# nttb.net
KiCad netlist of a schematic drawn in EAGLE
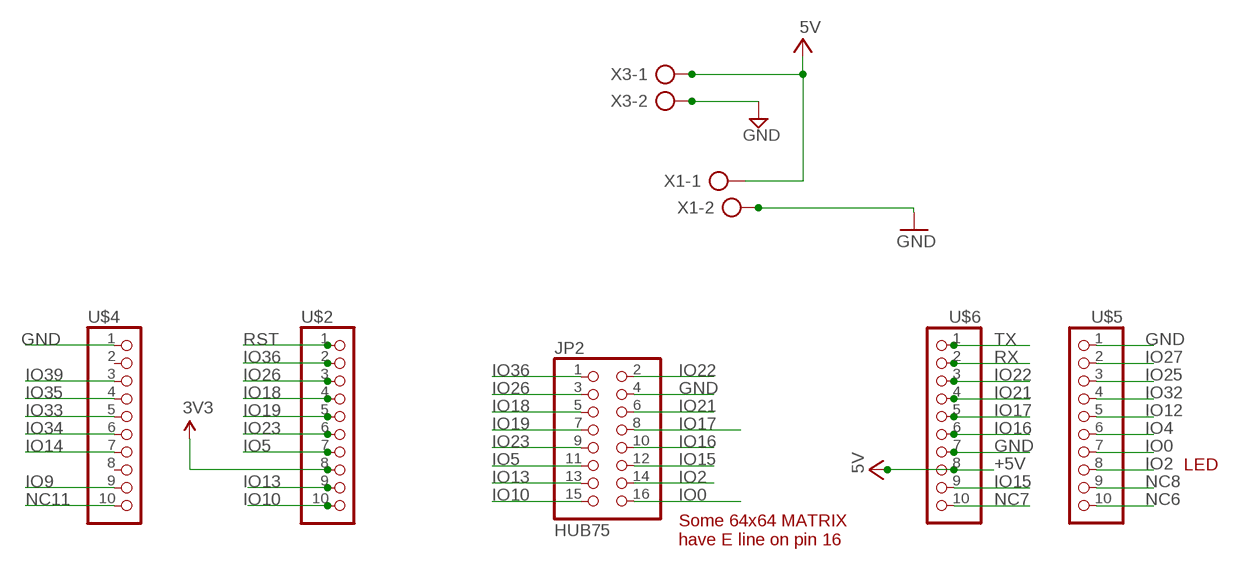
[diagram p0: schematic, sheet 1]

(export (version "E")
  (design (tool "Eeschema 10.0.6"))
  (components
    (comp (ref "JP2")
      (value "HUB75")
      (footprint "eagle-import:2X08")
      (libsource (lib "eagle-import") (part "HEADER-2X8"))
    )
    (comp (ref "U$2")
      (value "PINHD-1X10")
      (footprint "eagle-import:1X10-BIG")
      (libsource (lib "eagle-import") (part "PINHD-1X10"))
    )
    (comp (ref "U$4")
      (value "PINHD-1X10")
      (footprint "eagle-import:1X10-BIG")
      (libsource (lib "eagle-import") (part "PINHD-1X10"))
    )
    (comp (ref "U$5")
      (value "PINHD-1X10")
      (footprint "eagle-import:1X10-BIG")
      (libsource (lib "eagle-import") (part "PINHD-1X10"))
    )
    (comp (ref "U$6")
      (value "PINHD-1X10")
      (footprint "eagle-import:1X10-BIG")
      (libsource (lib "eagle-import") (part "PINHD-1X10"))
    )
    (comp (ref "X1")
      (value "AK500/2")
      (footprint "eagle-import:AK500_2")
      (libsource (lib "eagle-import") (part "AK500/2"))
    )
    (comp (ref "X3")
      (value "AK500/2")
      (footprint "eagle-import:AK500_2")
      (libsource (lib "eagle-import") (part "AK500/2"))
    )
  )
  (nets
    (net (code "1") (name "/IO0") (class "Default")
      (node (ref "JP2") (pin "16") (pinfunction "16_16") (pintype "passive"))
      (node (ref "U$5") (pin "7") (pinfunction "7_7") (pintype "passive"))
    )
    (net (code "2") (name "/IO2") (class "Default")
      (node (ref "JP2") (pin "14") (pinfunction "14_14") (pintype "passive"))
      (node (ref "U$5") (pin "8") (pinfunction "8_8") (pintype "passive"))
    )
    (net (code "3") (name "/IO4") (class "Default")
      (node (ref "U$5") (pin "6") (pinfunction "6_6") (pintype "passive"))
    )
    (net (code "4") (name "/IO5") (class "Default")
      (node (ref "JP2") (pin "11") (pinfunction "11_11") (pintype "passive"))
      (node (ref "U$2") (pin "7") (pinfunction "7_7") (pintype "passive"))
    )
    (net (code "5") (name "/IO9") (class "Default")
      (node (ref "U$4") (pin "9") (pinfunction "9_9") (pintype "passive"))
    )
    (net (code "6") (name "/IO10") (class "Default")
      (node (ref "JP2") (pin "15") (pinfunction "15_15") (pintype "passive"))
      (node (ref "U$2") (pin "10") (pinfunction "10_10") (pintype "passive"))
    )
    (net (code "7") (name "/IO12") (class "Default")
      (node (ref "U$5") (pin "5") (pinfunction "5_5") (pintype "passive"))
    )
    (net (code "8") (name "/IO13") (class "Default")
      (node (ref "JP2") (pin "13") (pinfunction "13_13") (pintype "passive"))
      (node (ref "U$2") (pin "9") (pinfunction "9_9") (pintype "passive"))
    )
    (net (code "9") (name "/IO14") (class "Default")
      (node (ref "U$4") (pin "7") (pinfunction "7_7") (pintype "passive"))
    )
    (net (code "10") (name "/IO15") (class "Default")
      (node (ref "JP2") (pin "12") (pinfunction "12_12") (pintype "passive"))
      (node (ref "U$6") (pin "9") (pinfunction "9_9") (pintype "passive"))
    )
    (net (code "11") (name "/IO16") (class "Default")
      (node (ref "JP2") (pin "10") (pinfunction "10_10") (pintype "passive"))
      (node (ref "U$6") (pin "6") (pinfunction "6_6") (pintype "passive"))
    )
    (net (code "12") (name "/IO17") (class "Default")
      (node (ref "JP2") (pin "8") (pinfunction "8_8") (pintype "passive"))
      (node (ref "U$6") (pin "5") (pinfunction "5_5") (pintype "passive"))
    )
    (net (code "13") (name "/IO18") (class "Default")
      (node (ref "JP2") (pin "5") (pinfunction "5_5") (pintype "passive"))
      (node (ref "U$2") (pin "4") (pinfunction "4_4") (pintype "passive"))
    )
    (net (code "14") (name "/IO19") (class "Default")
      (node (ref "JP2") (pin "7") (pinfunction "7_7") (pintype "passive"))
      (node (ref "U$2") (pin "5") (pinfunction "5_5") (pintype "passive"))
    )
    (net (code "15") (name "/IO21") (class "Default")
      (node (ref "JP2") (pin "6") (pinfunction "6_6") (pintype "passive"))
      (node (ref "U$6") (pin "4") (pinfunction "4_4") (pintype "passive"))
    )
    (net (code "16") (name "/IO22") (class "Default")
      (node (ref "JP2") (pin "2") (pinfunction "2_2") (pintype "passive"))
      (node (ref "U$6") (pin "3") (pinfunction "3_3") (pintype "passive"))
    )
    (net (code "17") (name "/IO23") (class "Default")
      (node (ref "JP2") (pin "9") (pinfunction "9_9") (pintype "passive"))
      (node (ref "U$2") (pin "6") (pinfunction "6_6") (pintype "passive"))
    )
    (net (code "18") (name "/IO25") (class "Default")
      (node (ref "U$5") (pin "3") (pinfunction "3_3") (pintype "passive"))
    )
    (net (code "19") (name "/IO26") (class "Default")
      (node (ref "JP2") (pin "3") (pinfunction "3_3") (pintype "passive"))
      (node (ref "U$2") (pin "3") (pinfunction "3_3") (pintype "passive"))
    )
    (net (code "20") (name "/IO27") (class "Default")
      (node (ref "U$5") (pin "2") (pinfunction "2_2") (pintype "passive"))
    )
    (net (code "21") (name "/IO32") (class "Default")
      (node (ref "U$5") (pin "4") (pinfunction "4_4") (pintype "passive"))
    )
    (net (code "22") (name "/IO33") (class "Default")
      (node (ref "U$4") (pin "5") (pinfunction "5_5") (pintype "passive"))
    )
    (net (code "23") (name "/IO34") (class "Default")
      (node (ref "U$4") (pin "6") (pinfunction "6_6") (pintype "passive"))
    )
    (net (code "24") (name "/IO35") (class "Default")
      (node (ref "U$4") (pin "4") (pinfunction "4_4") (pintype "passive"))
    )
    (net (code "25") (name "/IO36") (class "Default")
      (node (ref "JP2") (pin "1") (pinfunction "1_1") (pintype "passive"))
      (node (ref "U$2") (pin "2") (pinfunction "2_2") (pintype "passive"))
    )
    (net (code "26") (name "/IO39") (class "Default")
      (node (ref "U$4") (pin "3") (pinfunction "3_3") (pintype "passive"))
    )
    (net (code "27") (name "/NC6") (class "Default")
      (node (ref "U$5") (pin "10") (pinfunction "10_10") (pintype "passive"))
    )
    (net (code "28") (name "/NC7") (class "Default")
      (node (ref "U$6") (pin "10") (pinfunction "10_10") (pintype "passive"))
    )
    (net (code "29") (name "/NC8") (class "Default")
      (node (ref "U$5") (pin "9") (pinfunction "9_9") (pintype "passive"))
    )
    (net (code "30") (name "/NC11") (class "Default")
      (node (ref "U$4") (pin "10") (pinfunction "10_10") (pintype "passive"))
    )
    (net (code "31") (name "/RST") (class "Default")
      (node (ref "U$2") (pin "1") (pinfunction "1_1") (pintype "passive"))
    )
    (net (code "32") (name "/RX") (class "Default")
      (node (ref "U$6") (pin "2") (pinfunction "2_2") (pintype "passive"))
    )
    (net (code "33") (name "/TX") (class "Default")
      (node (ref "U$6") (pin "1") (pinfunction "1_1") (pintype "passive"))
    )
    (net (code "34") (name "3V3") (class "Default")
      (node (ref "U$2") (pin "8") (pinfunction "8_8") (pintype "passive"))
    )
    (net (code "35") (name "5V") (class "Default")
      (node (ref "U$6") (pin "8") (pinfunction "8_8") (pintype "passive"))
      (node (ref "X1") (pin "1") (pinfunction "KL_1") (pintype "passive"))
      (node (ref "X3") (pin "1") (pinfunction "KL_1") (pintype "passive"))
    )
    (net (code "36") (name "GND") (class "Default")
      (node (ref "JP2") (pin "4") (pinfunction "4_4") (pintype "passive"))
      (node (ref "U$4") (pin "1") (pinfunction "1_1") (pintype "passive"))
      (node (ref "U$5") (pin "1") (pinfunction "1_1") (pintype "passive"))
      (node (ref "U$6") (pin "7") (pinfunction "7_7") (pintype "passive"))
      (node (ref "X1") (pin "2") (pinfunction "KL_2") (pintype "passive"))
      (node (ref "X3") (pin "2") (pinfunction "KL_2") (pintype "passive"))
    )
    (net (code "37") (name "unconnected-(U$4-Pad2)") (class "Default")
      (node (ref "U$4") (pin "2") (pinfunction "2_2") (pintype "passive"))
    )
    (net (code "38") (name "unconnected-(U$4-Pad8)") (class "Default")
      (node (ref "U$4") (pin "8") (pinfunction "8_8") (pintype "passive"))
    )
  )
)
